# BarBot_2012_Tower.net
KiCad netlist of a schematic drawn in EAGLE
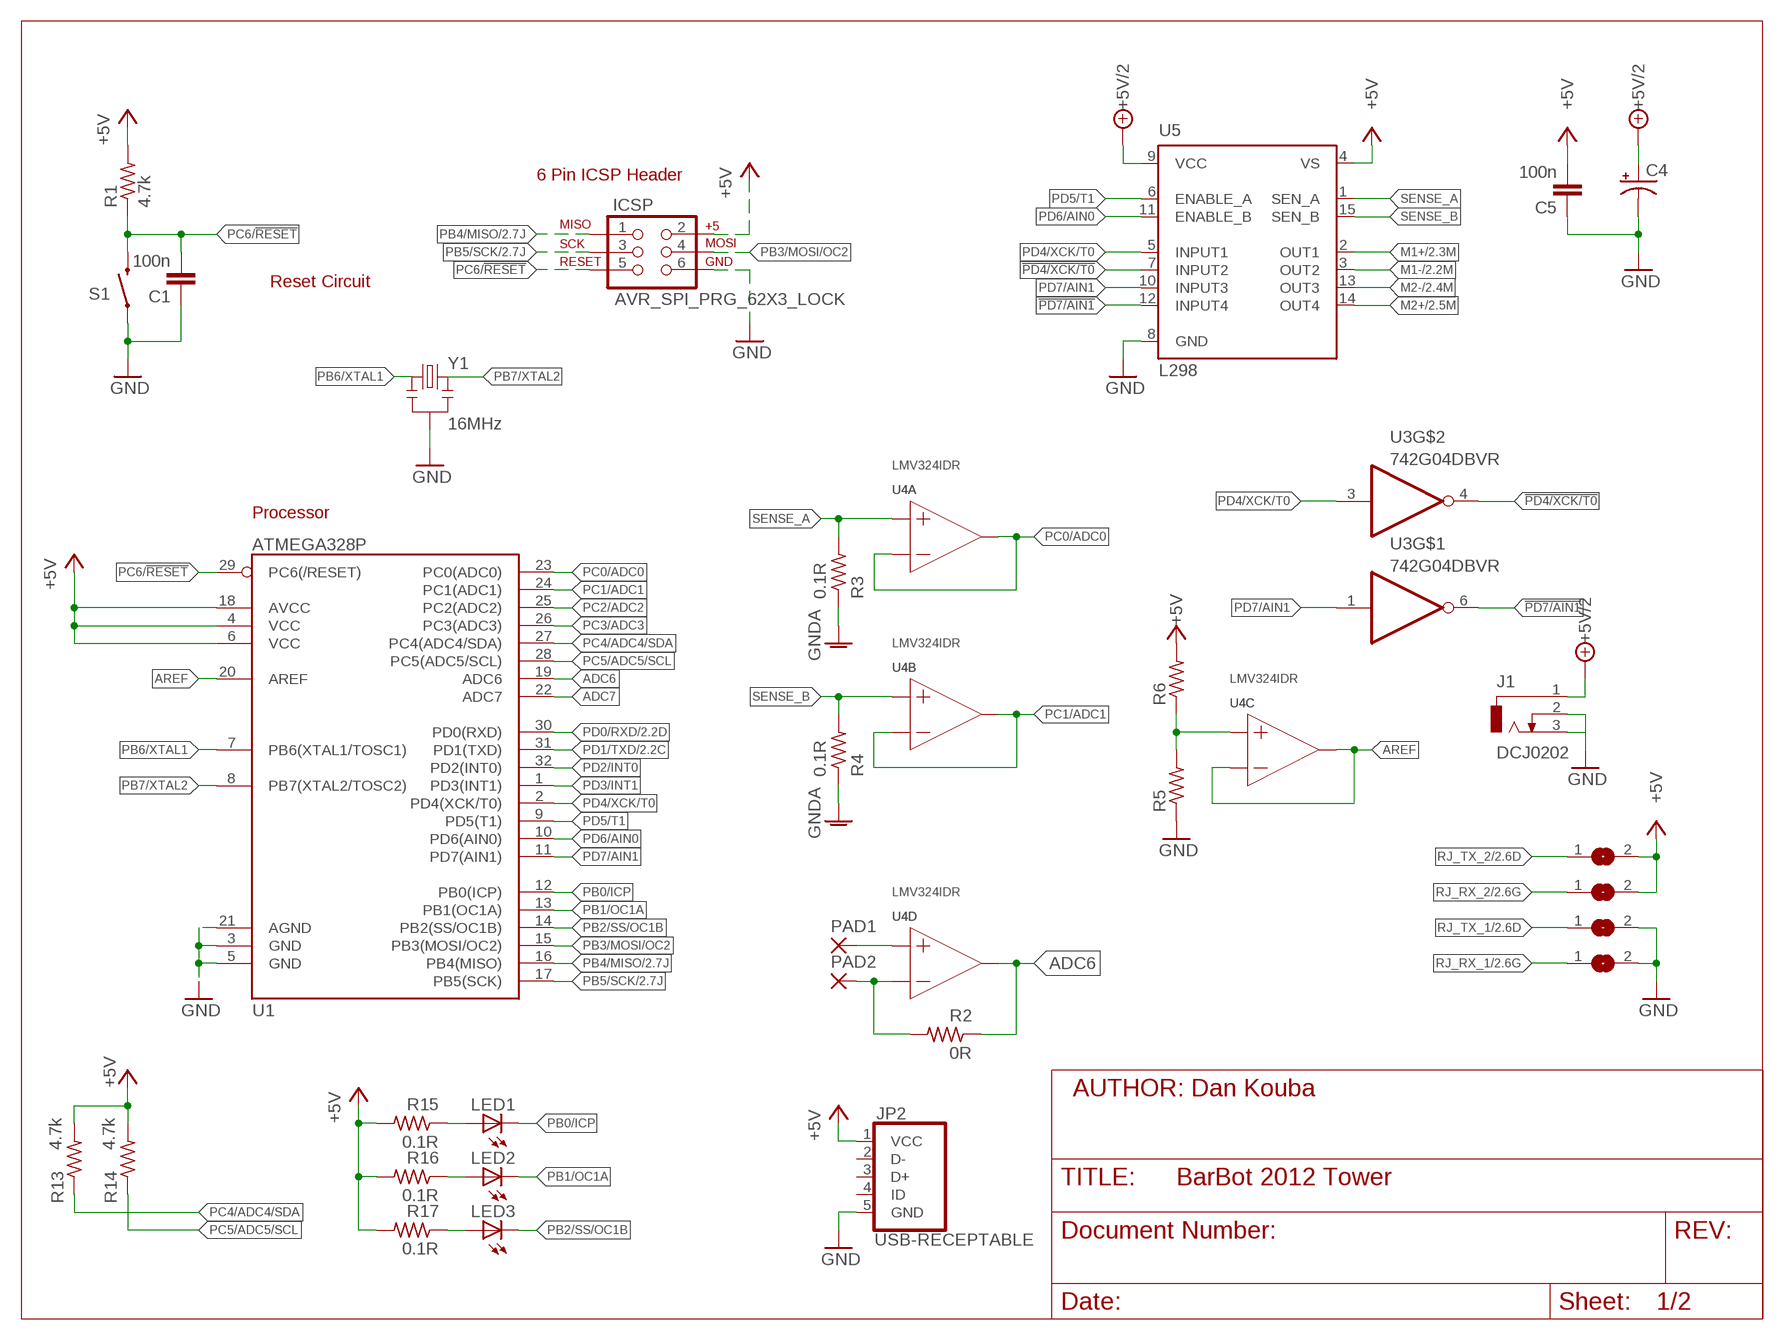
[diagram p0: schematic, sheet 1]
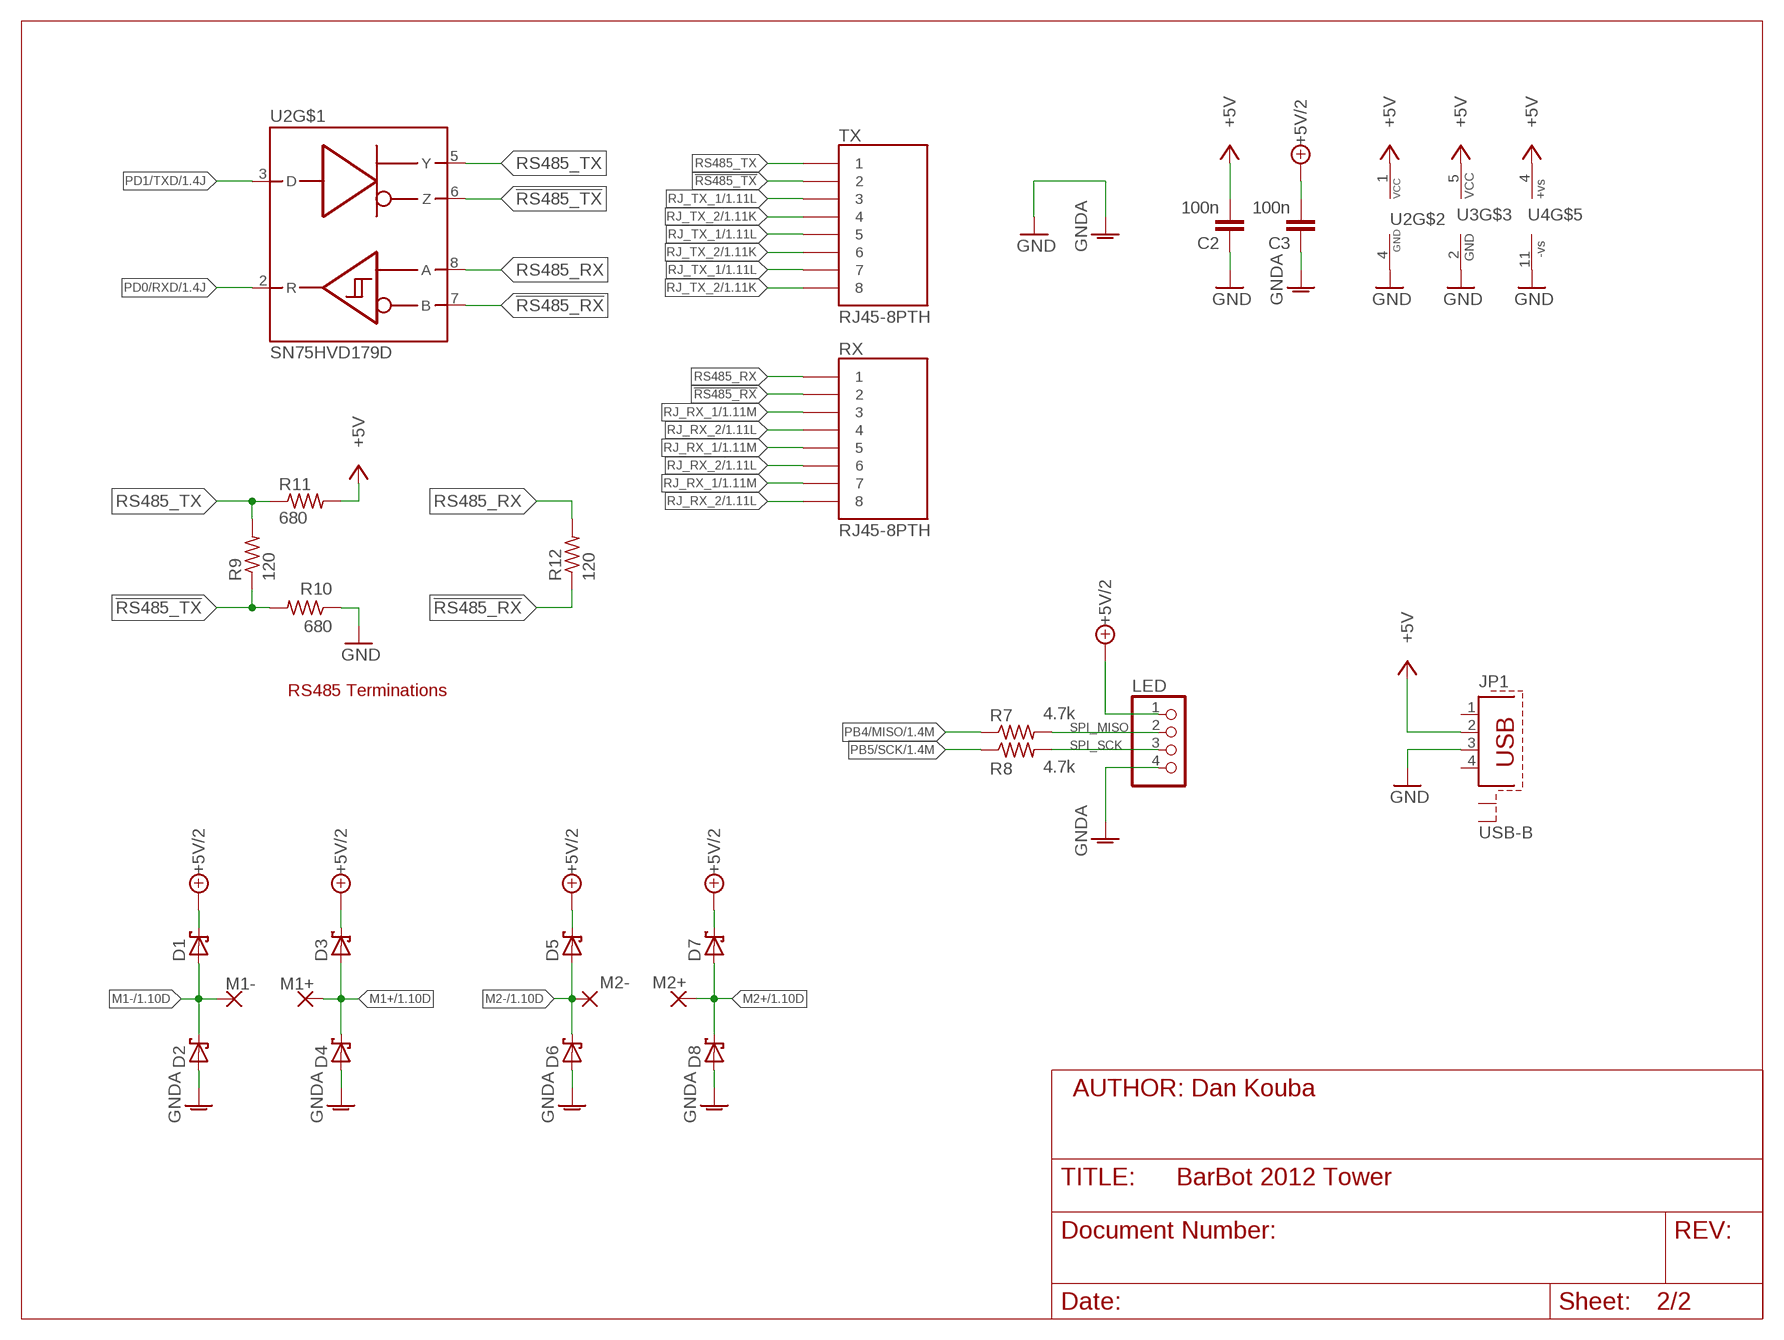
[diagram p1: schematic, sheet 2]

(export (version "E")
  (design (tool "Eeschema 10.0.6"))
  (components
    (comp (ref "C1")
      (value "100n")
      (footprint "eagle-import:C0805")
      (libsource (lib "eagle-import") (part "C-EUC0805"))
    )
    (comp (ref "C4")
      (value "CPOL-USE3.5-8")
      (footprint "eagle-import:E3,5-8")
      (libsource (lib "eagle-import") (part "CPOL-USE3.5-8"))
    )
    (comp (ref "C5")
      (value "100n")
      (footprint "eagle-import:C0805")
      (libsource (lib "eagle-import") (part "C-EUC0805"))
    )
    (comp (ref "ICSP")
      (value "AVR_SPI_PRG_62X3_LOCK")
      (footprint "eagle-import:2X3_LOCK")
      (libsource (lib "eagle-import") (part "AVR_SPI_PRG_62X3_LOCK"))
    )
    (comp (ref "J1")
      (value "DCJ0202")
      (footprint "eagle-import:DCJ0202")
      (libsource (lib "eagle-import") (part "DCJ0202"))
    )
    (comp (ref "JP2")
      (value "USB-RECEPTABLE")
      (footprint "eagle-import:FCI-10103594-0001LF")
      (libsource (lib "eagle-import") (part "USB-RECEPTABLE"))
    )
    (comp (ref "LED1")
      (value "LEDCHIPLED_0805")
      (footprint "eagle-import:CHIPLED_0805")
      (libsource (lib "eagle-import") (part "LEDCHIPLED_0805"))
    )
    (comp (ref "LED2")
      (value "LEDCHIPLED_0805")
      (footprint "eagle-import:CHIPLED_0805")
      (libsource (lib "eagle-import") (part "LEDCHIPLED_0805"))
    )
    (comp (ref "LED3")
      (value "LEDCHIPLED_0805")
      (footprint "eagle-import:CHIPLED_0805")
      (libsource (lib "eagle-import") (part "LEDCHIPLED_0805"))
    )
    (comp (ref "PAD1")
      (value "1,6/0,8")
      (footprint "eagle-import:1,6_0,8")
      (libsource (lib "eagle-import") (part "1,6/0,8"))
    )
    (comp (ref "PAD2")
      (value "1,6/0,8")
      (footprint "eagle-import:1,6_0,8")
      (libsource (lib "eagle-import") (part "1,6/0,8"))
    )
    (comp (ref "R1")
      (value "4.7k")
      (footprint "eagle-import:R0805")
      (libsource (lib "eagle-import") (part "R-US_R0805"))
    )
    (comp (ref "R2")
      (value "0R")
      (footprint "eagle-import:R0805")
      (libsource (lib "eagle-import") (part "R-US_R0805"))
    )
    (comp (ref "R3")
      (value "0.1R")
      (footprint "eagle-import:R0805")
      (libsource (lib "eagle-import") (part "R-US_R0805"))
    )
    (comp (ref "R4")
      (value "0.1R")
      (footprint "eagle-import:R0805")
      (libsource (lib "eagle-import") (part "R-US_R0805"))
    )
    (comp (ref "R5")
      (value "R-US_R0805")
      (footprint "eagle-import:R0805")
      (libsource (lib "eagle-import") (part "R-US_R0805"))
    )
    (comp (ref "R6")
      (value "R-US_R0805")
      (footprint "eagle-import:R0805")
      (libsource (lib "eagle-import") (part "R-US_R0805"))
    )
    (comp (ref "R13")
      (value "4.7k")
      (footprint "eagle-import:R0805")
      (libsource (lib "eagle-import") (part "R-US_R0805"))
    )
    (comp (ref "R14")
      (value "4.7k")
      (footprint "eagle-import:R0805")
      (libsource (lib "eagle-import") (part "R-US_R0805"))
    )
    (comp (ref "R15")
      (value "0.1R")
      (footprint "eagle-import:R0805")
      (libsource (lib "eagle-import") (part "R-US_R0805"))
    )
    (comp (ref "R16")
      (value "0.1R")
      (footprint "eagle-import:R0805")
      (libsource (lib "eagle-import") (part "R-US_R0805"))
    )
    (comp (ref "R17")
      (value "0.1R")
      (footprint "eagle-import:R0805")
      (libsource (lib "eagle-import") (part "R-US_R0805"))
    )
    (comp (ref "S1")
      (value "SWITCH-MOMENTARY-2PTH")
      (footprint "eagle-import:TACTILE-PTH")
      (libsource (lib "eagle-import") (part "SWITCH-MOMENTARY-2PTH"))
    )
    (comp (ref "SJ1") (value "SJ") (footprint "eagle-import:SJ") (libsource (lib "eagle-import") (part "SJ")))
    (comp (ref "SJ2") (value "SJ") (footprint "eagle-import:SJ") (libsource (lib "eagle-import") (part "SJ")))
    (comp (ref "SJ3") (value "SJ") (footprint "eagle-import:SJ") (libsource (lib "eagle-import") (part "SJ")))
    (comp (ref "SJ4") (value "SJ") (footprint "eagle-import:SJ") (libsource (lib "eagle-import") (part "SJ")))
    (comp (ref "U1")
      (value "ATMEGA328P")
      (footprint "eagle-import:TQFP32-08")
      (libsource (lib "eagle-import") (part "ATMEGA328_SMT"))
    )
    (comp (ref "U3")
      (value "742G04DBVR")
      (footprint "eagle-import:DBV_R-PDSO-G6")
      (libsource (lib "eagle-import") (part "742G04DBVR"))
    )
    (comp (ref "U4")
      (value "LMV324IDR")
      (footprint "eagle-import:SO14")
      (libsource (lib "eagle-import") (part "LMV324IDR"))
    )
    (comp (ref "U5")
      (value "L298")
      (footprint "eagle-import:MULTIWATT-15")
      (fields (field (name "MPN") "L298N"))
      (libsource (lib "eagle-import") (part "L298"))
    )
    (comp (ref "Y1")
      (value "16MHz")
      (footprint "eagle-import:RESONATOR-SMD")
      (libsource (lib "eagle-import") (part "RESONATOR16MHZ"))
    )
    (comp (ref "C2")
      (value "100n")
      (footprint "eagle-import:C0805")
      (libsource (lib "eagle-import") (part "C-EUC0805"))
    )
    (comp (ref "C3")
      (value "100n")
      (footprint "eagle-import:C0805")
      (libsource (lib "eagle-import") (part "C-EUC0805"))
    )
    (comp (ref "D1")
      (value "SCHOTTKY-DIODESMD")
      (footprint "eagle-import:SMB")
      (libsource (lib "eagle-import") (part "SCHOTTKY-DIODESMD"))
    )
    (comp (ref "D2")
      (value "SCHOTTKY-DIODESMD")
      (footprint "eagle-import:SMB")
      (libsource (lib "eagle-import") (part "SCHOTTKY-DIODESMD"))
    )
    (comp (ref "D3")
      (value "SCHOTTKY-DIODESMD")
      (footprint "eagle-import:SMB")
      (libsource (lib "eagle-import") (part "SCHOTTKY-DIODESMD"))
    )
    (comp (ref "D4")
      (value "SCHOTTKY-DIODESMD")
      (footprint "eagle-import:SMB")
      (libsource (lib "eagle-import") (part "SCHOTTKY-DIODESMD"))
    )
    (comp (ref "D5")
      (value "SCHOTTKY-DIODESMD")
      (footprint "eagle-import:SMB")
      (libsource (lib "eagle-import") (part "SCHOTTKY-DIODESMD"))
    )
    (comp (ref "D6")
      (value "SCHOTTKY-DIODESMD")
      (footprint "eagle-import:SMB")
      (libsource (lib "eagle-import") (part "SCHOTTKY-DIODESMD"))
    )
    (comp (ref "D7")
      (value "SCHOTTKY-DIODESMD")
      (footprint "eagle-import:SMB")
      (libsource (lib "eagle-import") (part "SCHOTTKY-DIODESMD"))
    )
    (comp (ref "D8")
      (value "SCHOTTKY-DIODESMD")
      (footprint "eagle-import:SMB")
      (libsource (lib "eagle-import") (part "SCHOTTKY-DIODESMD"))
    )
    (comp (ref "JP1")
      (value "USB-B")
      (footprint "eagle-import:PN61729-S")
      (libsource (lib "eagle-import") (part "PN61729-S"))
    )
    (comp (ref "LED")
      (value "PINHD-1X4")
      (footprint "eagle-import:1X04")
      (libsource (lib "eagle-import") (part "PINHD-1X4"))
    )
    (comp (ref "M1+")
      (value "3,81/1,1")
      (footprint "eagle-import:3,81_1,1")
      (libsource (lib "eagle-import") (part "3,81/1,1"))
    )
    (comp (ref "M1-")
      (value "3,81/1,1")
      (footprint "eagle-import:3,81_1,1")
      (libsource (lib "eagle-import") (part "3,81/1,1"))
    )
    (comp (ref "M2+")
      (value "3,81/1,1")
      (footprint "eagle-import:3,81_1,1")
      (libsource (lib "eagle-import") (part "3,81/1,1"))
    )
    (comp (ref "M2-")
      (value "3,81/1,1")
      (footprint "eagle-import:3,81_1,1")
      (libsource (lib "eagle-import") (part "3,81/1,1"))
    )
    (comp (ref "R7")
      (value "4.7k")
      (footprint "eagle-import:R0805")
      (libsource (lib "eagle-import") (part "R-US_R0805"))
    )
    (comp (ref "R8")
      (value "4.7k")
      (footprint "eagle-import:R0805")
      (libsource (lib "eagle-import") (part "R-US_R0805"))
    )
    (comp (ref "R9")
      (value "120")
      (footprint "eagle-import:R0805")
      (libsource (lib "eagle-import") (part "R-US_R0805"))
    )
    (comp (ref "R10")
      (value "680")
      (footprint "eagle-import:R0805")
      (libsource (lib "eagle-import") (part "R-US_R0805"))
    )
    (comp (ref "R11")
      (value "680")
      (footprint "eagle-import:R0805")
      (libsource (lib "eagle-import") (part "R-US_R0805"))
    )
    (comp (ref "R12")
      (value "120")
      (footprint "eagle-import:R0805")
      (libsource (lib "eagle-import") (part "R-US_R0805"))
    )
    (comp (ref "RX")
      (value "RJ45-8PTH")
      (footprint "eagle-import:RJ45-8")
      (libsource (lib "eagle-import") (part "RJ45-8PTH"))
    )
    (comp (ref "TX")
      (value "RJ45-8PTH")
      (footprint "eagle-import:RJ45-8")
      (libsource (lib "eagle-import") (part "RJ45-8PTH"))
    )
    (comp (ref "U2")
      (value "SN75HVD179D")
      (footprint "eagle-import:SO-08")
      (libsource (lib "eagle-import") (part "SN75HVD179D"))
    )
  )
  (nets
    (net (code "1") (name "+5V") (class "Default")
      (node (ref "C2") (pin "2") (pinfunction "2_2") (pintype "passive"))
      (node (ref "C5") (pin "2") (pinfunction "2_2") (pintype "passive"))
      (node (ref "ICSP") (pin "2") (pinfunction "2_2") (pintype "passive"))
      (node (ref "JP1") (pin "2") (pinfunction "2_2") (pintype "passive"))
      (node (ref "JP2") (pin "1") (pinfunction "VCC_1") (pintype "bidirectional"))
      (node (ref "R1") (pin "2") (pinfunction "2_2") (pintype "passive"))
      (node (ref "R11") (pin "2") (pinfunction "2_2") (pintype "passive"))
      (node (ref "R13") (pin "2") (pinfunction "2_2") (pintype "passive"))
      (node (ref "R14") (pin "2") (pinfunction "2_2") (pintype "passive"))
      (node (ref "R15") (pin "2") (pinfunction "2_2") (pintype "passive"))
      (node (ref "R16") (pin "2") (pinfunction "2_2") (pintype "passive"))
      (node (ref "R17") (pin "2") (pinfunction "2_2") (pintype "passive"))
      (node (ref "R6") (pin "2") (pinfunction "2_2") (pintype "passive"))
      (node (ref "SJ3") (pin "2") (pinfunction "2_2") (pintype "passive"))
      (node (ref "SJ4") (pin "2") (pinfunction "2_2") (pintype "passive"))
      (node (ref "U1") (pin "18") (pinfunction "AVCC_18") (pintype "bidirectional"))
      (node (ref "U1") (pin "4") (pinfunction "VCC_4") (pintype "bidirectional"))
      (node (ref "U1") (pin "6") (pinfunction "VCC_6") (pintype "bidirectional"))
      (node (ref "U2") (pin "1") (pinfunction "VCC_1") (pintype "power_in"))
      (node (ref "U3") (pin "5") (pinfunction "VCC_5") (pintype "power_in"))
      (node (ref "U4") (pin "4") (pinfunction "+VS_4") (pintype "power_in"))
      (node (ref "U5") (pin "4") (pinfunction "VS_4") (pintype "power_in"))
    )
    (net (code "2") (name "+5V{slash}2") (class "Default")
      (node (ref "C3") (pin "2") (pinfunction "2_2") (pintype "passive"))
      (node (ref "C4") (pin "+") (pinfunction "+_+") (pintype "passive"))
      (node (ref "D1") (pin "C") (pinfunction "C_C") (pintype "passive"))
      (node (ref "D3") (pin "C") (pinfunction "C_C") (pintype "passive"))
      (node (ref "D5") (pin "C") (pinfunction "C_C") (pintype "passive"))
      (node (ref "D7") (pin "C") (pinfunction "C_C") (pintype "passive"))
      (node (ref "J1") (pin "1") (pinfunction "1_1") (pintype "passive"))
      (node (ref "LED") (pin "1") (pinfunction "1_1") (pintype "passive"))
      (node (ref "U5") (pin "9") (pinfunction "VCC_9") (pintype "power_in"))
    )
    (net (code "3") (name "ADC6") (class "Default")
      (node (ref "R2") (pin "1") (pinfunction "1_1") (pintype "passive"))
      (node (ref "U1") (pin "19") (pinfunction "ADC6_19") (pintype "bidirectional"))
      (node (ref "U4") (pin "14") (pinfunction "OUT_14") (pintype "power_in"))
    )
    (net (code "4") (name "ADC7") (class "Default")
      (node (ref "U1") (pin "22") (pinfunction "ADC7_22") (pintype "bidirectional"))
    )
    (net (code "5") (name "AREF") (class "Default")
      (node (ref "U1") (pin "20") (pinfunction "AREF_20") (pintype "bidirectional"))
      (node (ref "U4") (pin "8") (pinfunction "OUT_8") (pintype "power_in"))
      (node (ref "U4") (pin "9") (pinfunction "-IN_9") (pintype "power_in"))
    )
    (net (code "6") (name "GND") (class "Default")
      (node (ref "C1") (pin "1") (pinfunction "1_1") (pintype "passive"))
      (node (ref "C2") (pin "1") (pinfunction "1_1") (pintype "passive"))
      (node (ref "C3") (pin "1") (pinfunction "1_1") (pintype "passive"))
      (node (ref "C4") (pin "-") (pinfunction "-_-") (pintype "passive"))
      (node (ref "C5") (pin "1") (pinfunction "1_1") (pintype "passive"))
      (node (ref "D2") (pin "A") (pinfunction "A_A") (pintype "passive"))
      (node (ref "D4") (pin "A") (pinfunction "A_A") (pintype "passive"))
      (node (ref "D6") (pin "A") (pinfunction "A_A") (pintype "passive"))
      (node (ref "D8") (pin "A") (pinfunction "A_A") (pintype "passive"))
      (node (ref "ICSP") (pin "6") (pinfunction "6_6") (pintype "passive"))
      (node (ref "J1") (pin "2") (pinfunction "2_2") (pintype "passive"))
      (node (ref "J1") (pin "3") (pinfunction "3_3") (pintype "passive"))
      (node (ref "JP1") (pin "3") (pinfunction "3_3") (pintype "passive"))
      (node (ref "JP2") (pin "5") (pinfunction "GND_5") (pintype "bidirectional"))
      (node (ref "LED") (pin "4") (pinfunction "4_4") (pintype "passive"))
      (node (ref "R10") (pin "1") (pinfunction "1_1") (pintype "passive"))
      (node (ref "R3") (pin "1") (pinfunction "1_1") (pintype "passive"))
      (node (ref "R4") (pin "1") (pinfunction "1_1") (pintype "passive"))
      (node (ref "R5") (pin "1") (pinfunction "1_1") (pintype "passive"))
      (node (ref "S1") (pin "1") (pinfunction "1_1") (pintype "passive"))
      (node (ref "SJ1") (pin "2") (pinfunction "2_2") (pintype "passive"))
      (node (ref "SJ2") (pin "2") (pinfunction "2_2") (pintype "passive"))
      (node (ref "U1") (pin "21") (pinfunction "AGND_21") (pintype "bidirectional"))
      (node (ref "U1") (pin "3") (pinfunction "GND_3") (pintype "bidirectional"))
      (node (ref "U1") (pin "5") (pinfunction "GND_5") (pintype "bidirectional"))
      (node (ref "U2") (pin "4") (pinfunction "GND_4") (pintype "power_in"))
      (node (ref "U3") (pin "2") (pinfunction "GND_2") (pintype "power_in"))
      (node (ref "U4") (pin "11") (pinfunction "-VS_11") (pintype "power_in"))
      (node (ref "U5") (pin "8") (pinfunction "GND_8") (pintype "power_in"))
      (node (ref "Y1") (pin "2") (pinfunction "2_2") (pintype "passive"))
    )
    (net (code "7") (name "M1+") (class "Default")
      (node (ref "D3") (pin "A") (pinfunction "A_A") (pintype "passive"))
      (node (ref "D4") (pin "C") (pinfunction "C_C") (pintype "passive"))
      (node (ref "M1+") (pin "1") (pinfunction "P_1") (pintype "passive"))
      (node (ref "U5") (pin "2") (pinfunction "OUT1_2") (pintype "output"))
    )
    (net (code "8") (name "M1-") (class "Default")
      (node (ref "D1") (pin "A") (pinfunction "A_A") (pintype "passive"))
      (node (ref "D2") (pin "C") (pinfunction "C_C") (pintype "passive"))
      (node (ref "M1-") (pin "1") (pinfunction "P_1") (pintype "passive"))
      (node (ref "U5") (pin "3") (pinfunction "OUT2_3") (pintype "output"))
    )
    (net (code "9") (name "M2+") (class "Default")
      (node (ref "D7") (pin "A") (pinfunction "A_A") (pintype "passive"))
      (node (ref "D8") (pin "C") (pinfunction "C_C") (pintype "passive"))
      (node (ref "M2+") (pin "1") (pinfunction "P_1") (pintype "passive"))
      (node (ref "U5") (pin "14") (pinfunction "OUT4_14") (pintype "output"))
    )
    (net (code "10") (name "M2-") (class "Default")
      (node (ref "D5") (pin "A") (pinfunction "A_A") (pintype "passive"))
      (node (ref "D6") (pin "C") (pinfunction "C_C") (pintype "passive"))
      (node (ref "M2-") (pin "1") (pinfunction "P_1") (pintype "passive"))
      (node (ref "U5") (pin "13") (pinfunction "OUT3_13") (pintype "output"))
    )
    (net (code "11") (name "Net-(LED1-PadA)") (class "Default")
      (node (ref "LED1") (pin "A") (pinfunction "A_A") (pintype "passive"))
      (node (ref "R15") (pin "1") (pinfunction "1_1") (pintype "passive"))
    )
    (net (code "12") (name "Net-(LED2-PadA)") (class "Default")
      (node (ref "LED2") (pin "A") (pinfunction "A_A") (pintype "passive"))
      (node (ref "R16") (pin "1") (pinfunction "1_1") (pintype "passive"))
    )
    (net (code "13") (name "Net-(LED3-PadA)") (class "Default")
      (node (ref "LED3") (pin "A") (pinfunction "A_A") (pintype "passive"))
      (node (ref "R17") (pin "1") (pinfunction "1_1") (pintype "passive"))
    )
    (net (code "14") (name "Net-(PAD1-P)") (class "Default")
      (node (ref "PAD1") (pin "1") (pinfunction "P_1") (pintype "passive"))
      (node (ref "U4") (pin "12") (pinfunction "+IN_12") (pintype "power_in"))
    )
    (net (code "15") (name "Net-(PAD2-P)") (class "Default")
      (node (ref "PAD2") (pin "1") (pinfunction "P_1") (pintype "passive"))
      (node (ref "R2") (pin "2") (pinfunction "2_2") (pintype "passive"))
      (node (ref "U4") (pin "13") (pinfunction "-IN_13") (pintype "power_in"))
    )
    (net (code "16") (name "Net-(U4C-+IN)") (class "Default")
      (node (ref "R5") (pin "2") (pinfunction "2_2") (pintype "passive"))
      (node (ref "R6") (pin "1") (pinfunction "1_1") (pintype "passive"))
      (node (ref "U4") (pin "10") (pinfunction "+IN_10") (pintype "power_in"))
    )
    (net (code "17") (name "PB0{slash}ICP") (class "Default")
      (node (ref "LED1") (pin "C") (pinfunction "C_C") (pintype "passive"))
      (node (ref "U1") (pin "12") (pinfunction "PB0(ICP)_12") (pintype "bidirectional"))
    )
    (net (code "18") (name "PB1{slash}OC1A") (class "Default")
      (node (ref "LED2") (pin "C") (pinfunction "C_C") (pintype "passive"))
      (node (ref "U1") (pin "13") (pinfunction "PB1(OC1A)_13") (pintype "bidirectional"))
    )
    (net (code "19") (name "PB2{slash}SS{slash}OC1B") (class "Default")
      (node (ref "LED3") (pin "C") (pinfunction "C_C") (pintype "passive"))
      (node (ref "U1") (pin "14") (pinfunction "PB2(SS/OC1B)_14") (pintype "bidirectional"))
    )
    (net (code "20") (name "PB3{slash}MOSI{slash}OC2") (class "Default")
      (node (ref "ICSP") (pin "4") (pinfunction "4_4") (pintype "passive"))
      (node (ref "U1") (pin "15") (pinfunction "PB3(MOSI/OC2)_15") (pintype "bidirectional"))
    )
    (net (code "21") (name "PB4{slash}MISO") (class "Default")
      (node (ref "ICSP") (pin "1") (pinfunction "1_1") (pintype "passive"))
      (node (ref "R7") (pin "1") (pinfunction "1_1") (pintype "passive"))
      (node (ref "U1") (pin "16") (pinfunction "PB4(MISO)_16") (pintype "bidirectional"))
    )
    (net (code "22") (name "PB5{slash}SCK") (class "Default")
      (node (ref "ICSP") (pin "3") (pinfunction "3_3") (pintype "passive"))
      (node (ref "R8") (pin "1") (pinfunction "1_1") (pintype "passive"))
      (node (ref "U1") (pin "17") (pinfunction "PB5(SCK)_17") (pintype "bidirectional"))
    )
    (net (code "23") (name "PB6{slash}XTAL1") (class "Default")
      (node (ref "U1") (pin "7") (pinfunction "PB6(XTAL1/TOSC1)_7") (pintype "bidirectional"))
      (node (ref "Y1") (pin "1") (pinfunction "1_1") (pintype "passive"))
    )
    (net (code "24") (name "PB7{slash}XTAL2") (class "Default")
      (node (ref "U1") (pin "8") (pinfunction "PB7(XTAL2/TOSC2)_8") (pintype "bidirectional"))
      (node (ref "Y1") (pin "3") (pinfunction "3_3") (pintype "passive"))
    )
    (net (code "25") (name "PC0{slash}ADC0") (class "Default")
      (node (ref "U1") (pin "23") (pinfunction "PC0(ADC0)_23") (pintype "bidirectional"))
      (node (ref "U4") (pin "1") (pinfunction "OUT_1") (pintype "power_in"))
      (node (ref "U4") (pin "2") (pinfunction "-IN_2") (pintype "power_in"))
    )
    (net (code "26") (name "PC1{slash}ADC1") (class "Default")
      (node (ref "U1") (pin "24") (pinfunction "PC1(ADC1)_24") (pintype "bidirectional"))
      (node (ref "U4") (pin "6") (pinfunction "-IN_6") (pintype "power_in"))
      (node (ref "U4") (pin "7") (pinfunction "OUT_7") (pintype "power_in"))
    )
    (net (code "27") (name "PC2{slash}ADC2") (class "Default")
      (node (ref "U1") (pin "25") (pinfunction "PC2(ADC2)_25") (pintype "bidirectional"))
    )
    (net (code "28") (name "PC3{slash}ADC3") (class "Default")
      (node (ref "U1") (pin "26") (pinfunction "PC3(ADC3)_26") (pintype "bidirectional"))
    )
    (net (code "29") (name "PC4{slash}ADC4{slash}SDA") (class "Default")
      (node (ref "R13") (pin "1") (pinfunction "1_1") (pintype "passive"))
      (node (ref "U1") (pin "27") (pinfunction "PC4(ADC4/SDA)_27") (pintype "bidirectional"))
    )
    (net (code "30") (name "PC5{slash}ADC5{slash}SCL") (class "Default")
      (node (ref "R14") (pin "1") (pinfunction "1_1") (pintype "passive"))
      (node (ref "U1") (pin "28") (pinfunction "PC5(ADC5/SCL)_28") (pintype "bidirectional"))
    )
    (net (code "31") (name "PC6{slash}~{RESET}") (class "Default")
      (node (ref "C1") (pin "2") (pinfunction "2_2") (pintype "passive"))
      (node (ref "ICSP") (pin "5") (pinfunction "5_5") (pintype "passive"))
      (node (ref "R1") (pin "1") (pinfunction "1_1") (pintype "passive"))
      (node (ref "S1") (pin "3") (pinfunction "2_3") (pintype "passive"))
      (node (ref "U1") (pin "29") (pinfunction "PC6(/RESET)_29") (pintype "bidirectional"))
    )
    (net (code "32") (name "PD0{slash}RXD") (class "Default")
      (node (ref "U1") (pin "30") (pinfunction "PD0(RXD)_30") (pintype "bidirectional"))
      (node (ref "U2") (pin "2") (pinfunction "R_2") (pintype "output"))
    )
    (net (code "33") (name "PD1{slash}TXD") (class "Default")
      (node (ref "U1") (pin "31") (pinfunction "PD1(TXD)_31") (pintype "bidirectional"))
      (node (ref "U2") (pin "3") (pinfunction "D_3") (pintype "input"))
    )
    (net (code "34") (name "PD2{slash}INT0") (class "Default")
      (node (ref "U1") (pin "32") (pinfunction "PD2(INT0)_32") (pintype "bidirectional"))
    )
    (net (code "35") (name "PD3{slash}INT1") (class "Default")
      (node (ref "U1") (pin "1") (pinfunction "PD3(INT1)_1") (pintype "bidirectional"))
    )
    (net (code "36") (name "PD4{slash}XCK{slash}T0") (class "Default")
      (node (ref "U1") (pin "2") (pinfunction "PD4(XCK/T0)_2") (pintype "bidirectional"))
      (node (ref "U3") (pin "3") (pinfunction "I_3") (pintype "input"))
      (node (ref "U5") (pin "5") (pinfunction "INPUT1_5") (pintype "input"))
    )
    (net (code "37") (name "PD5{slash}T1") (class "Default")
      (node (ref "U1") (pin "9") (pinfunction "PD5(T1)_9") (pintype "bidirectional"))
      (node (ref "U5") (pin "6") (pinfunction "ENABLE_A_6") (pintype "input"))
    )
    (net (code "38") (name "PD6{slash}AIN0") (class "Default")
      (node (ref "U1") (pin "10") (pinfunction "PD6(AIN0)_10") (pintype "bidirectional"))
      (node (ref "U5") (pin "11") (pinfunction "ENABLE_B_11") (pintype "input"))
    )
    (net (code "39") (name "PD7{slash}AIN1") (class "Default")
      (node (ref "U1") (pin "11") (pinfunction "PD7(AIN1)_11") (pintype "bidirectional"))
      (node (ref "U3") (pin "1") (pinfunction "I_1") (pintype "input"))
      (node (ref "U5") (pin "10") (pinfunction "INPUT3_10") (pintype "input"))
    )
    (net (code "40") (name "RJ_RX_1") (class "Default")
      (node (ref "RX") (pin "3") (pinfunction "3_3") (pintype "bidirectional"))
      (node (ref "RX") (pin "5") (pinfunction "5_5") (pintype "bidirectional"))
      (node (ref "RX") (pin "7") (pinfunction "7_7") (pintype "bidirectional"))
      (node (ref "SJ2") (pin "1") (pinfunction "1_1") (pintype "passive"))
    )
    (net (code "41") (name "RJ_RX_2") (class "Default")
      (node (ref "RX") (pin "4") (pinfunction "4_4") (pintype "bidirectional"))
      (node (ref "RX") (pin "6") (pinfunction "6_6") (pintype "bidirectional"))
      (node (ref "RX") (pin "8") (pinfunction "8_8") (pintype "bidirectional"))
      (node (ref "SJ4") (pin "1") (pinfunction "1_1") (pintype "passive"))
    )
    (net (code "42") (name "RJ_TX_1") (class "Default")
      (node (ref "SJ1") (pin "1") (pinfunction "1_1") (pintype "passive"))
      (node (ref "TX") (pin "3") (pinfunction "3_3") (pintype "bidirectional"))
      (node (ref "TX") (pin "5") (pinfunction "5_5") (pintype "bidirectional"))
      (node (ref "TX") (pin "7") (pinfunction "7_7") (pintype "bidirectional"))
    )
    (net (code "43") (name "RJ_TX_2") (class "Default")
      (node (ref "SJ3") (pin "1") (pinfunction "1_1") (pintype "passive"))
      (node (ref "TX") (pin "4") (pinfunction "4_4") (pintype "bidirectional"))
      (node (ref "TX") (pin "6") (pinfunction "6_6") (pintype "bidirectional"))
      (node (ref "TX") (pin "8") (pinfunction "8_8") (pintype "bidirectional"))
    )
    (net (code "44") (name "RS485_RX") (class "Default")
      (node (ref "R12") (pin "2") (pinfunction "2_2") (pintype "passive"))
      (node (ref "RX") (pin "1") (pinfunction "1_1") (pintype "bidirectional"))
      (node (ref "U2") (pin "8") (pinfunction "A_8") (pintype "input"))
    )
    (net (code "45") (name "RS485_TX") (class "Default")
      (node (ref "R11") (pin "1") (pinfunction "1_1") (pintype "passive"))
      (node (ref "R9") (pin "2") (pinfunction "2_2") (pintype "passive"))
      (node (ref "TX") (pin "1") (pinfunction "1_1") (pintype "bidirectional"))
      (node (ref "U2") (pin "5") (pinfunction "Y_5") (pintype "output"))
    )
    (net (code "46") (name "SENSE_A") (class "Default")
      (node (ref "R3") (pin "2") (pinfunction "2_2") (pintype "passive"))
      (node (ref "U4") (pin "3") (pinfunction "+IN_3") (pintype "power_in"))
      (node (ref "U5") (pin "1") (pinfunction "SEN_A_1") (pintype "input"))
    )
    (net (code "47") (name "SENSE_B") (class "Default")
      (node (ref "R4") (pin "2") (pinfunction "2_2") (pintype "passive"))
      (node (ref "U4") (pin "5") (pinfunction "+IN_5") (pintype "power_in"))
      (node (ref "U5") (pin "15") (pinfunction "SEN_B_15") (pintype "input"))
    )
    (net (code "48") (name "SPI_MISO") (class "Default")
      (node (ref "LED") (pin "2") (pinfunction "2_2") (pintype "passive"))
      (node (ref "R7") (pin "2") (pinfunction "2_2") (pintype "passive"))
    )
    (net (code "49") (name "SPI_SCK") (class "Default")
      (node (ref "LED") (pin "3") (pinfunction "3_3") (pintype "passive"))
      (node (ref "R8") (pin "2") (pinfunction "2_2") (pintype "passive"))
    )
    (net (code "50") (name "unconnected-(JP1-Pad1)") (class "Default")
      (node (ref "JP1") (pin "1") (pinfunction "1_1") (pintype "passive"))
    )
    (net (code "51") (name "unconnected-(JP1-Pad4)") (class "Default")
      (node (ref "JP1") (pin "4") (pinfunction "4_4") (pintype "passive"))
    )
    (net (code "52") (name "unconnected-(JP1-PadS1)") (class "Default")
      (node (ref "JP1") (pin "S1") (pinfunction "S1_S1") (pintype "passive"))
    )
    (net (code "53") (name "unconnected-(JP1-PadS2)") (class "Default")
      (node (ref "JP1") (pin "S2") (pinfunction "S2_S2") (pintype "passive"))
    )
    (net (code "54") (name "unconnected-(JP2-D+-Pad3)") (class "Default")
      (node (ref "JP2") (pin "3") (pinfunction "D+_3") (pintype "bidirectional"))
    )
    (net (code "55") (name "unconnected-(JP2-D--Pad2)") (class "Default")
      (node (ref "JP2") (pin "2") (pinfunction "D-_2") (pintype "bidirectional"))
    )
    (net (code "56") (name "unconnected-(JP2-ID-Pad4)") (class "Default")
      (node (ref "JP2") (pin "4") (pinfunction "ID_4") (pintype "bidirectional"))
    )
    (net (code "57") (name "~{PD4{slash}XCK{slash}T0}") (class "Default")
      (node (ref "U3") (pin "4") (pinfunction "O_4") (pintype "output"))
      (node (ref "U5") (pin "7") (pinfunction "INPUT2_7") (pintype "input"))
    )
    (net (code "58") (name "~{PD7{slash}AIN1}") (class "Default")
      (node (ref "U3") (pin "6") (pinfunction "O_6") (pintype "output"))
      (node (ref "U5") (pin "12") (pinfunction "INPUT4_12") (pintype "input"))
    )
    (net (code "59") (name "~{RS485_RX}") (class "Default")
      (node (ref "R12") (pin "1") (pinfunction "1_1") (pintype "passive"))
      (node (ref "RX") (pin "2") (pinfunction "2_2") (pintype "bidirectional"))
      (node (ref "U2") (pin "7") (pinfunction "B_7") (pintype "input"))
    )
    (net (code "60") (name "~{RS485_TX}") (class "Default")
      (node (ref "R10") (pin "2") (pinfunction "2_2") (pintype "passive"))
      (node (ref "R9") (pin "1") (pinfunction "1_1") (pintype "passive"))
      (node (ref "TX") (pin "2") (pinfunction "2_2") (pintype "bidirectional"))
      (node (ref "U2") (pin "6") (pinfunction "Z_6") (pintype "output"))
    )
  )
)
